# AIRZAI_BASE_BD_REVC_Sheet1.net
KiCad netlist of a schematic drawn in Altium Designer
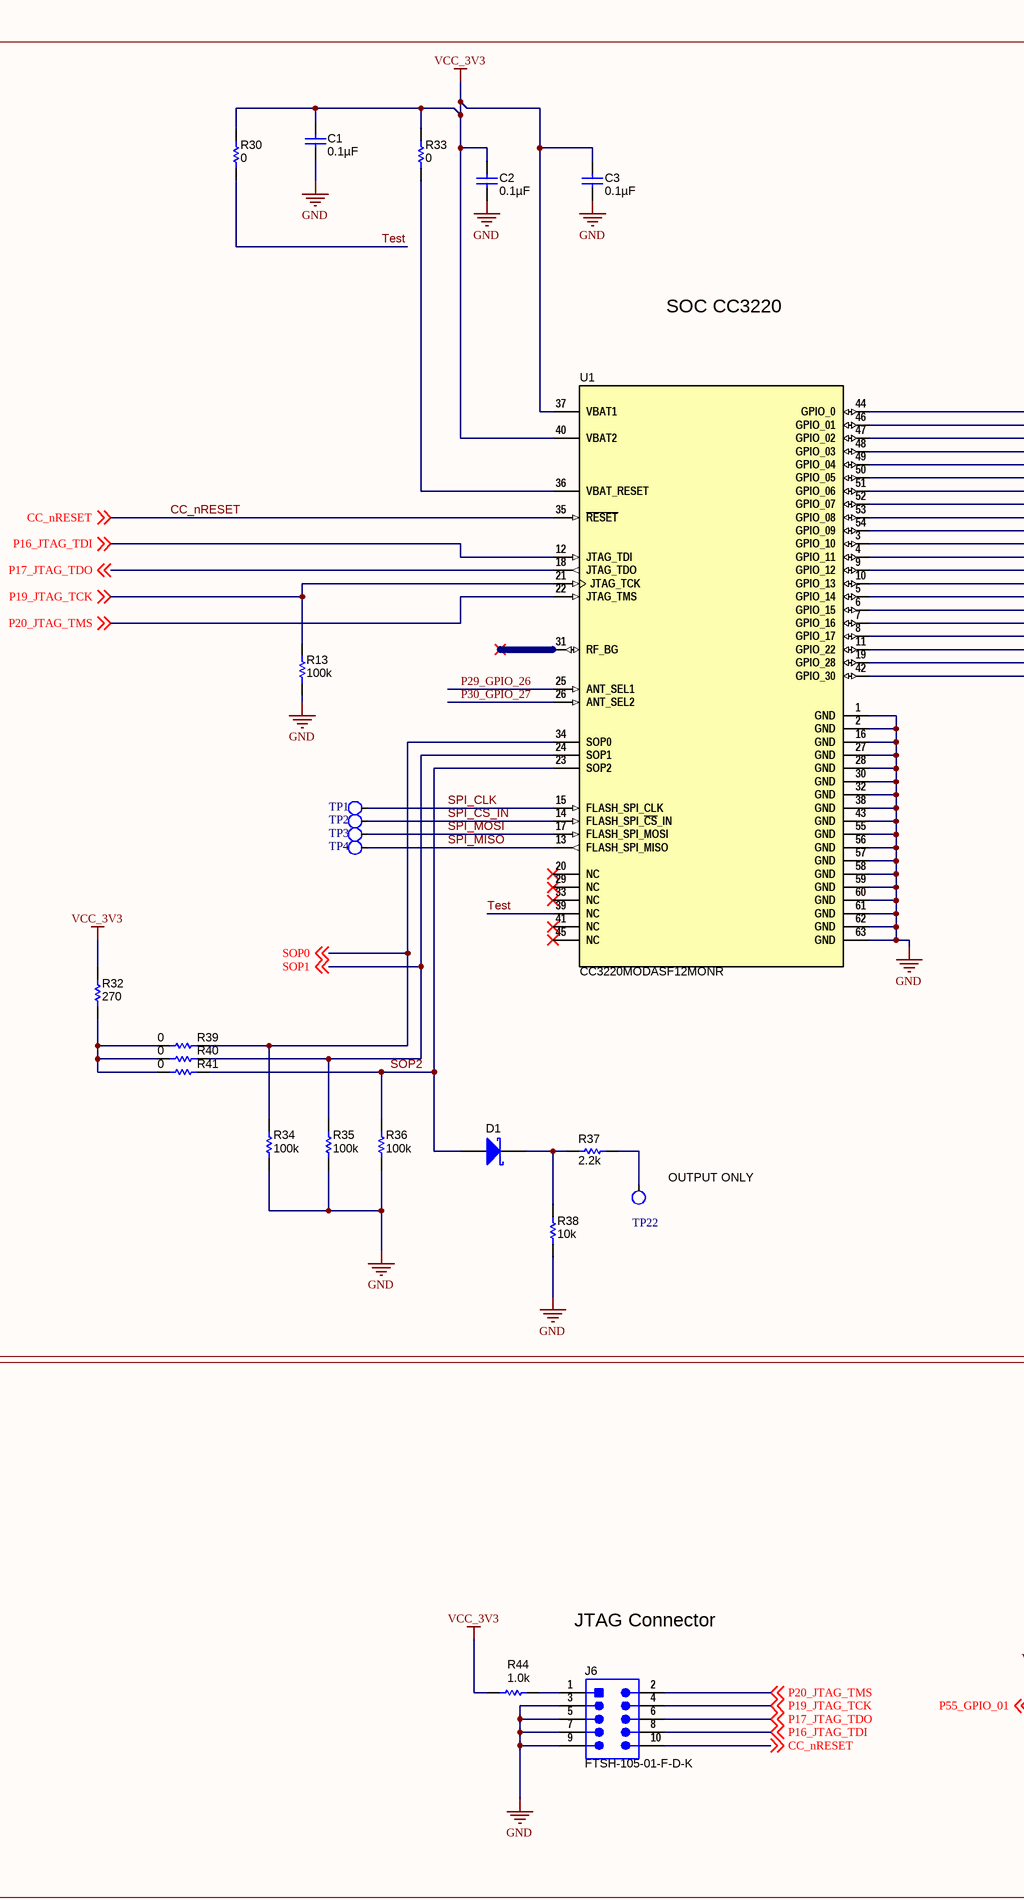
[diagram p0: AIRZAI_BASE_BD_REVC Sheet1.SchDoc, left]
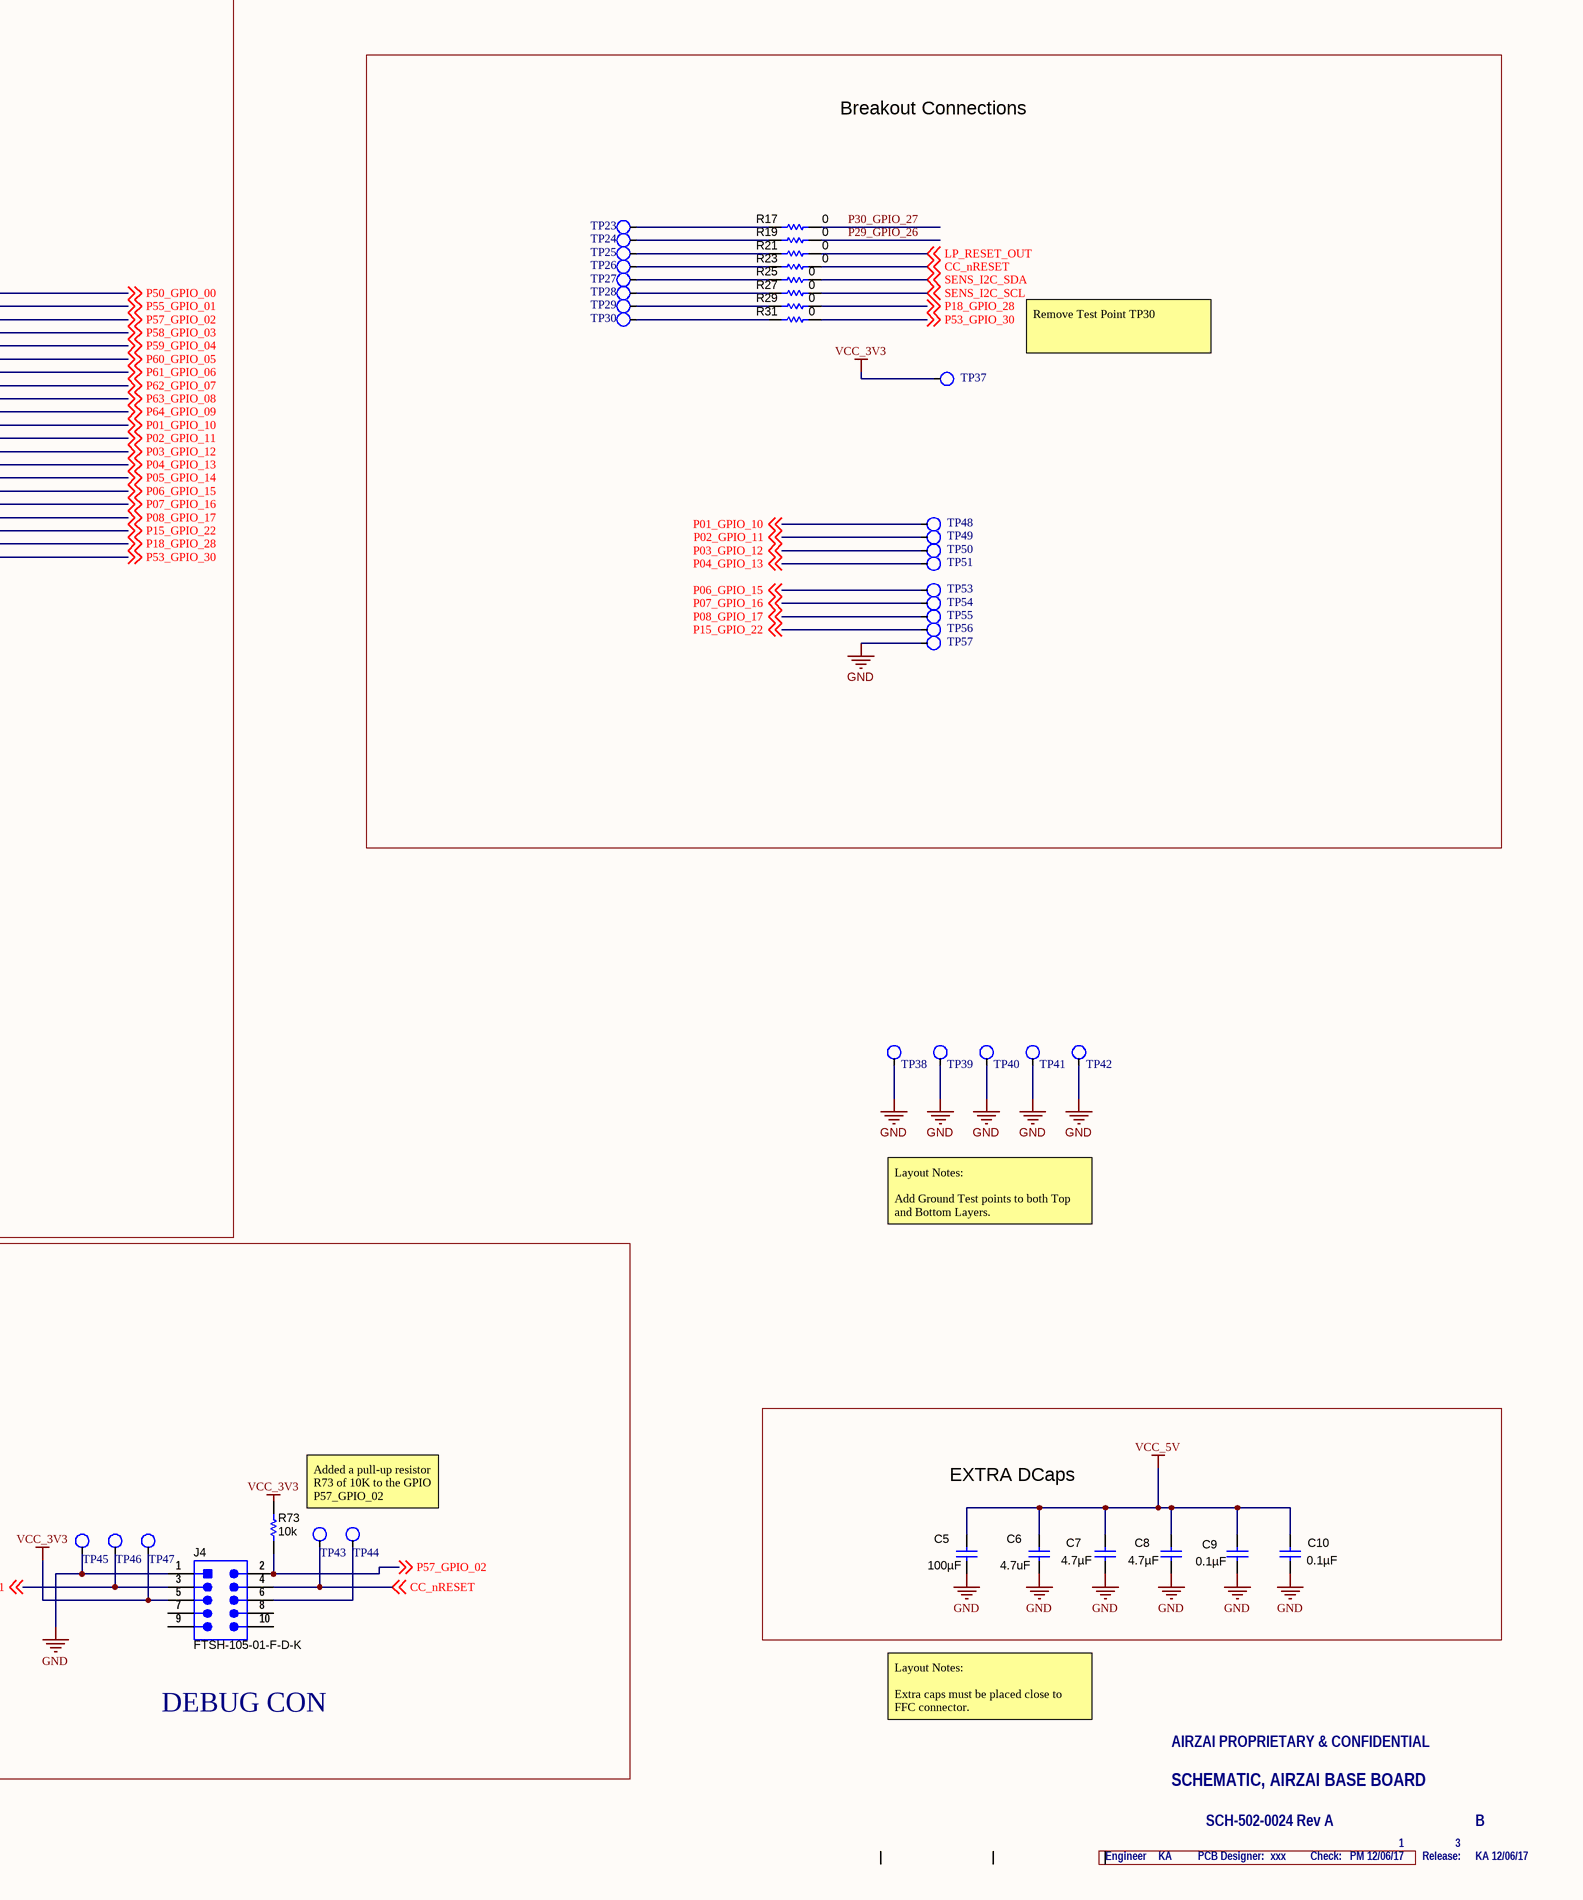
[diagram p1: AIRZAI_BASE_BD_REVC Sheet1.SchDoc, right]

(export (version "E")
  (design (tool "Eeschema 10.0.6"))
  (components
    (comp (ref "C1")
      (value "GRM155R61A104KA01D")
      (footprint "0402")
      (description "CAP, CERM, 0.1 µF, 10 V, +/- 10%, X5R, 0402")
      (fields
        (field (name "VALUEDISPLAYED") "0.1µF")
        (field (name "MANUFACTURER") "MuRata")
        (field (name "PUBLISHER") "Texas Instruments")
      )
      (libsource (lib "Capacitor_Ceramic") (part "GRM155R61A104KA01D"))
    )
    (comp (ref "C2")
      (value "GRM155R61A104KA01D")
      (footprint "0402")
      (description "CAP, CERM, 0.1 µF, 10 V, +/- 10%, X5R, 0402")
      (fields
        (field (name "VALUEDISPLAYED") "0.1µF")
        (field (name "MANUFACTURER") "MuRata")
        (field (name "PUBLISHER") "Texas Instruments")
      )
      (libsource (lib "Capacitor_Ceramic") (part "GRM155R61A104KA01D"))
    )
    (comp (ref "C3")
      (value "GRM155R61A104KA01D")
      (footprint "0402")
      (description "CAP, CERM, 0.1 µF, 10 V, +/- 10%, X5R, 0402")
      (fields
        (field (name "VALUEDISPLAYED") "0.1µF")
        (field (name "MANUFACTURER") "MuRata")
        (field (name "PUBLISHER") "Texas Instruments")
      )
      (libsource (lib "Capacitor_Ceramic") (part "GRM155R61A104KA01D"))
    )
    (comp (ref "C5")
      (value "GRM31CR60J107ME39L")
      (footprint "1206_180")
      (description "CAP, CERM, 100 µF, 6.3 V, +/- 20%, X5R, 1206")
      (fields
        (field (name "VALUEDISPLAYED") "100µF")
        (field (name "MANUFACTURER") "MuRata")
        (field (name "PUBLISHER") "Texas Instruments")
      )
      (libsource (lib "Capacitor_Ceramic") (part "GRM31CR60J107ME39L"))
    )
    (comp (ref "C6")
      (value "4.7uF")
      (footprint "SM0402_BTD.1SM_ACT_H55_CAP_WSS")
      (description "CAP, CERM, 4.7 µF, 6.3 V, +/- 20%, X5R, 0402")
      (fields (field (name "PARTNUMBER") "C1005X5R0J475M050BC") (field (name "MANUFACTURER") "TDK"))
      (libsource (lib "Capacitor_Ceramic") (part "C1005X5R0J475M050BC"))
    )
    (comp (ref "C7")
      (value "C1005X5R0J475M050BC")
      (footprint "SM0402_BTD.1SM_ACT_H55_CAP_WSS")
      (description "CAP, CERM, 4.7 µF, 6.3 V, +/- 20%, X5R, 0402")
      (fields
        (field (name "VALUEDISPLAYED") "4.7µF")
        (field (name "MANUFACTURER") "TDK")
        (field (name "PUBLISHER") "Texas Instruments")
      )
      (libsource (lib "Capacitor_Ceramic") (part "C1005X5R0J475M050BC"))
    )
    (comp (ref "C8")
      (value "C1005X5R0J475M050BC")
      (footprint "SM0402_BTD.1SM_ACT_H55_CAP_WSS")
      (description "CAP, CERM, 4.7 µF, 6.3 V, +/- 20%, X5R, 0402")
      (fields
        (field (name "VALUEDISPLAYED") "4.7µF")
        (field (name "MANUFACTURER") "TDK")
        (field (name "PUBLISHER") "Texas Instruments")
      )
      (libsource (lib "Capacitor_Ceramic") (part "C1005X5R0J475M050BC"))
    )
    (comp (ref "C9")
      (value "C1005X5R1A104K050BA")
      (footprint "SM0402_BTD.1SM_ACT_H55_CAP_WSS")
      (description "CAP, CERM, 0.1 µF, 10 V, +/- 10%, X5R, 0402")
      (fields
        (field (name "VALUEDISPLAYED") "0.1µF")
        (field (name "MANUFACTURER") "TDK")
        (field (name "PUBLISHER") "Texas Instruments")
      )
      (libsource (lib "Capacitor_Ceramic") (part "C1005X5R1A104K050BA"))
    )
    (comp (ref "C10")
      (value "C1005X5R1A104K050BA")
      (footprint "SM0402_BTD.1SM_ACT_H55_CAP_WSS")
      (description "CAP, CERM, 0.1 µF, 10 V, +/- 10%, X5R, 0402")
      (fields
        (field (name "VALUEDISPLAYED") "0.1µF")
        (field (name "MANUFACTURER") "TDK")
        (field (name "PUBLISHER") "Texas Instruments")
      )
      (libsource (lib "Capacitor_Ceramic") (part "C1005X5R1A104K050BA"))
    )
    (comp (ref "D1")
      (value "CD0603-B00340")
      (footprint "Diode_0603")
      (description "Diode, Schottky, 45 V, 0.03 A, 0603 Diode")
      (fields (field (name "MANUFACTURER") "Bourns") (field (name "PUBLISHER") "Texas Instruments"))
      (libsource (lib "Diode") (part "CD0603-B00340"))
    )
    (comp (ref "J4")
      (value "FTSH-105-01-F-D-K")
      (footprint "Samtec_FTSH-105-01-x-D-K")
      (description "Header, 1.27 mm, 5x2, Gold, TH")
      (fields
        (field (name "MANUFACTURER") "Samtec")
        (field (name "SYMBOLCREATOR") "a0412235")
        (field (name "PUBLISHER") "Texas Instruments")
      )
      (libsource (lib "Connectors_Samtec") (part "FTSH-105-01-F-D-K"))
    )
    (comp (ref "J6")
      (value "FTSH-105-01-F-D-K")
      (footprint "Samtec_FTSH-105-01-x-D-K")
      (description "Header, 1.27 mm, 5x2, Gold, TH")
      (fields
        (field (name "MANUFACTURER") "Samtec")
        (field (name "SYMBOLCREATOR") "a0412235")
        (field (name "PUBLISHER") "Texas Instruments")
      )
      (libsource (lib "Connectors_Samtec") (part "FTSH-105-01-F-D-K"))
    )
    (comp (ref "R13")
      (value "CRCW0402100KJNED")
      (footprint "0402")
      (description "RES, 100 k, 5%, 0.063 W, 0402")
      (fields
        (field (name "VALUEDISPLAYED") "100k")
        (field (name "MANUFACTURER") "Vishay-Dale")
        (field (name "PUBLISHER") "Texas Instruments")
      )
      (libsource (lib "Resistor_0402") (part "CRCW0402100KJNED"))
    )
    (comp (ref "R17")
      (value "ERJ-2GE0R00X")
      (footprint "0402")
      (description "RES, 0, 5%, 0.063 W, 0402")
      (fields
        (field (name "VALUEDISPLAYED") "0")
        (field (name "MANUFACTURER") "Panasonic")
        (field (name "PUBLISHER") "Texas Instruments")
      )
      (libsource (lib "Resistor_0402") (part "ERJ-2GE0R00X"))
    )
    (comp (ref "R19")
      (value "ERJ-2GE0R00X")
      (footprint "0402")
      (description "RES, 0, 5%, 0.063 W, 0402")
      (fields
        (field (name "VALUEDISPLAYED") "0")
        (field (name "MANUFACTURER") "Panasonic")
        (field (name "PUBLISHER") "Texas Instruments")
      )
      (libsource (lib "Resistor_0402") (part "ERJ-2GE0R00X"))
    )
    (comp (ref "R21")
      (value "ERJ-2GE0R00X")
      (footprint "0402")
      (description "RES, 0, 5%, 0.063 W, 0402")
      (fields
        (field (name "VALUEDISPLAYED") "0")
        (field (name "MANUFACTURER") "Panasonic")
        (field (name "PUBLISHER") "Texas Instruments")
      )
      (libsource (lib "Resistor_0402") (part "ERJ-2GE0R00X"))
    )
    (comp (ref "R23")
      (value "ERJ-2GE0R00X")
      (footprint "0402")
      (description "RES, 0, 5%, 0.063 W, 0402")
      (fields
        (field (name "VALUEDISPLAYED") "0")
        (field (name "MANUFACTURER") "Panasonic")
        (field (name "PUBLISHER") "Texas Instruments")
      )
      (libsource (lib "Resistor_0402") (part "ERJ-2GE0R00X"))
    )
    (comp (ref "R25")
      (value "ERJ-2GE0R00X")
      (footprint "0402")
      (description "RES, 0, 5%, 0.063 W, 0402")
      (fields
        (field (name "VALUEDISPLAYED") "0")
        (field (name "MANUFACTURER") "Panasonic")
        (field (name "PUBLISHER") "Texas Instruments")
      )
      (libsource (lib "Resistor_0402") (part "ERJ-2GE0R00X"))
    )
    (comp (ref "R27")
      (value "ERJ-2GE0R00X")
      (footprint "0402")
      (description "RES, 0, 5%, 0.063 W, 0402")
      (fields
        (field (name "VALUEDISPLAYED") "0")
        (field (name "MANUFACTURER") "Panasonic")
        (field (name "PUBLISHER") "Texas Instruments")
      )
      (libsource (lib "Resistor_0402") (part "ERJ-2GE0R00X"))
    )
    (comp (ref "R29")
      (value "ERJ-2GE0R00X")
      (footprint "0402")
      (description "RES, 0, 5%, 0.063 W, 0402")
      (fields
        (field (name "VALUEDISPLAYED") "0")
        (field (name "MANUFACTURER") "Panasonic")
        (field (name "PUBLISHER") "Texas Instruments")
      )
      (libsource (lib "Resistor_0402") (part "ERJ-2GE0R00X"))
    )
    (comp (ref "R30")
      (value "RC0603JR-070RL")
      (footprint "0603")
      (description "RES, 0, 5%, 0.1 W, 0603")
      (fields
        (field (name "VALUEDISPLAYED") "0")
        (field (name "MANUFACTURER") "Yageo")
        (field (name "TOLERANCE") "1%")
      )
      (libsource (lib "Resistor_0402") (part "ERJ-2GE0R00X"))
    )
    (comp (ref "R31")
      (value "ERJ-2GE0R00X")
      (footprint "0402")
      (description "RES, 0, 5%, 0.063 W, 0402")
      (fields
        (field (name "VALUEDISPLAYED") "0")
        (field (name "MANUFACTURER") "Panasonic")
        (field (name "PUBLISHER") "Texas Instruments")
      )
      (libsource (lib "Resistor_0402") (part "ERJ-2GE0R00X"))
    )
    (comp (ref "R32")
      (value "CRCW0402270RJNED")
      (footprint "0402")
      (description "RES, 270, 5%, 0.063 W, 0402")
      (fields
        (field (name "VALUEDISPLAYED") "270")
        (field (name "MANUFACTURER") "Vishay-Dale")
        (field (name "PUBLISHER") "Texas Instruments")
      )
      (libsource (lib "Resistor_0402") (part "CRCW0402270RJNED"))
    )
    (comp (ref "R33")
      (value "RC0603JR-070RL")
      (footprint "0603")
      (description "RES, 0, 5%, 0.1 W, 0603")
      (fields
        (field (name "VALUEDISPLAYED") "0")
        (field (name "MANUFACTURER") "Yageo")
        (field (name "TOLERANCE") "1%")
      )
      (libsource (lib "Resistor_0402") (part "ERJ-2GE0R00X"))
    )
    (comp (ref "R34")
      (value "CRCW0402100KJNED")
      (footprint "0402")
      (description "RES, 100 k, 5%, 0.063 W, 0402")
      (fields
        (field (name "VALUEDISPLAYED") "100k")
        (field (name "MANUFACTURER") "Vishay-Dale")
        (field (name "PUBLISHER") "Texas Instruments")
      )
      (libsource (lib "Resistor_0402") (part "CRCW0402100KJNED"))
    )
    (comp (ref "R35")
      (value "CRCW0402100KJNED")
      (footprint "0402")
      (description "RES, 100 k, 5%, 0.063 W, 0402")
      (fields
        (field (name "VALUEDISPLAYED") "100k")
        (field (name "MANUFACTURER") "Vishay-Dale")
        (field (name "PUBLISHER") "Texas Instruments")
      )
      (libsource (lib "Resistor_0402") (part "CRCW0402100KJNED"))
    )
    (comp (ref "R36")
      (value "CRCW0402100KJNED")
      (footprint "0402")
      (description "RES, 100 k, 5%, 0.063 W, 0402")
      (fields
        (field (name "VALUEDISPLAYED") "100k")
        (field (name "MANUFACTURER") "Vishay-Dale")
        (field (name "PUBLISHER") "Texas Instruments")
      )
      (libsource (lib "Resistor_0402") (part "CRCW0402100KJNED"))
    )
    (comp (ref "R37")
      (value "CRCW04022K20JNED")
      (footprint "0402")
      (description "RES, 2.2 k, 5%, 0.063 W, 0402")
      (fields
        (field (name "VALUEDISPLAYED") "2.2k")
        (field (name "MANUFACTURER") "Vishay-Dale")
        (field (name "PUBLISHER") "Texas Instruments")
      )
      (libsource (lib "Resistor_0402") (part "CRCW04022K20JNED"))
    )
    (comp (ref "R38")
      (value "CRCW040210K0JNED")
      (footprint "0402")
      (description "RES, 10 k, 5%, 0.063 W, 0402")
      (fields
        (field (name "VALUEDISPLAYED") "10k")
        (field (name "MANUFACTURER") "Vishay-Dale")
        (field (name "PUBLISHER") "Texas Instruments")
      )
      (libsource (lib "Resistor_0402") (part "CRCW040210K0JNED"))
    )
    (comp (ref "R39")
      (value "RC0603JR-070RL")
      (footprint "0603")
      (description "RES, 0, 5%, 0.1 W, 0603")
      (fields
        (field (name "VALUEDISPLAYED") "0")
        (field (name "MANUFACTURER") "Yageo")
        (field (name "TOLERANCE") "1%")
      )
      (libsource (lib "Resistor_0402") (part "ERJ-2GE0R00X"))
    )
    (comp (ref "R40")
      (value "RC0603JR-070RL")
      (footprint "0603")
      (description "RES, 0, 5%, 0.1 W, 0603")
      (fields
        (field (name "VALUEDISPLAYED") "0")
        (field (name "MANUFACTURER") "Yageo")
        (field (name "TOLERANCE") "1%")
      )
      (libsource (lib "Resistor_0402") (part "ERJ-2GE0R00X"))
    )
    (comp (ref "R41")
      (value "RC0603JR-070RL")
      (footprint "0603")
      (description "RES, 0, 5%, 0.1 W, 0603")
      (fields
        (field (name "VALUEDISPLAYED") "0")
        (field (name "MANUFACTURER") "Yageo")
        (field (name "TOLERANCE") "1%")
      )
      (libsource (lib "Resistor_0402") (part "ERJ-2GE0R00X"))
    )
    (comp (ref "R44")
      (value "CRCW04021K00JNED")
      (footprint "0402")
      (description "RES, 1.0 k, 5%, 0.063 W, 0402")
      (fields
        (field (name "VALUEDISPLAYED") "1.0k")
        (field (name "MANUFACTURER") "Vishay-Dale")
        (field (name "PUBLISHER") "Texas Instruments")
      )
      (libsource (lib "Resistor_0402") (part "CRCW04021K00JNED"))
    )
    (comp (ref "R73")
      (value "CRCW040210K0JNED")
      (footprint "0402")
      (description "RES, 10 k, 5%, 0.063 W, 0402")
      (fields
        (field (name "VALUEDISPLAYED") "10k")
        (field (name "MANUFACTURER") "Vishay-Dale")
        (field (name "PUBLISHER") "Texas Instruments")
      )
      (libsource (lib "Resistor_0402") (part "CRCW040210K0JNED"))
    )
    (comp (ref "TP1")
      (value "WIREPT")
      (footprint "TP_0.9MM")
      (libsource (lib "EAGLE_CAD_Library") (part "WIREPT"))
    )
    (comp (ref "TP2")
      (value "WIREPT")
      (footprint "TP_0.9MM")
      (libsource (lib "EAGLE_CAD_Library") (part "WIREPT"))
    )
    (comp (ref "TP3")
      (value "WIREPT")
      (footprint "TP_0.9MM")
      (libsource (lib "EAGLE_CAD_Library") (part "WIREPT"))
    )
    (comp (ref "TP4")
      (value "WIREPT")
      (footprint "TP_0.9MM")
      (libsource (lib "EAGLE_CAD_Library") (part "WIREPT"))
    )
    (comp (ref "TP22")
      (value "WIREPT")
      (footprint "TP_0.9MM")
      (libsource (lib "EAGLE_CAD_Library") (part "WIREPT"))
    )
    (comp (ref "TP23")
      (value "WIREPT")
      (footprint "TP_0.9MM")
      (libsource (lib "EAGLE_CAD_Library") (part "WIREPT"))
    )
    (comp (ref "TP24")
      (value "WIREPT")
      (footprint "TP_0.9MM")
      (libsource (lib "EAGLE_CAD_Library") (part "WIREPT"))
    )
    (comp (ref "TP25")
      (value "WIREPT")
      (footprint "TP_0.9MM")
      (libsource (lib "EAGLE_CAD_Library") (part "WIREPT"))
    )
    (comp (ref "TP26")
      (value "WIREPT")
      (footprint "TP_0.9MM")
      (libsource (lib "EAGLE_CAD_Library") (part "WIREPT"))
    )
    (comp (ref "TP27")
      (value "WIREPT")
      (footprint "TP_0.9MM")
      (libsource (lib "EAGLE_CAD_Library") (part "WIREPT"))
    )
    (comp (ref "TP28")
      (value "WIREPT")
      (footprint "TP_0.9MM")
      (libsource (lib "EAGLE_CAD_Library") (part "WIREPT"))
    )
    (comp (ref "TP29")
      (value "WIREPT")
      (footprint "TP_0.9MM")
      (libsource (lib "EAGLE_CAD_Library") (part "WIREPT"))
    )
    (comp (ref "TP30")
      (value "WIREPT")
      (footprint "TP_0.9MM")
      (libsource (lib "EAGLE_CAD_Library") (part "WIREPT"))
    )
    (comp (ref "TP37")
      (value "WIREPT")
      (footprint "TP_0.9MM")
      (libsource (lib "EAGLE_CAD_Library") (part "WIREPT"))
    )
    (comp (ref "TP38")
      (value "WIREPT")
      (footprint "TP_0.9MM")
      (libsource (lib "EAGLE_CAD_Library") (part "WIREPT"))
    )
    (comp (ref "TP39")
      (value "WIREPT")
      (footprint "TP_0.9MM")
      (libsource (lib "EAGLE_CAD_Library") (part "WIREPT"))
    )
    (comp (ref "TP40")
      (value "WIREPT")
      (footprint "TP_0.9MM")
      (libsource (lib "EAGLE_CAD_Library") (part "WIREPT"))
    )
    (comp (ref "TP41")
      (value "WIREPT")
      (footprint "TP_0.9MM")
      (libsource (lib "EAGLE_CAD_Library") (part "WIREPT"))
    )
    (comp (ref "TP42")
      (value "WIREPT")
      (footprint "TP_0.9MM")
      (libsource (lib "EAGLE_CAD_Library") (part "WIREPT"))
    )
    (comp (ref "TP43")
      (value "WIREPT")
      (footprint "TP_0.9MM")
      (libsource (lib "EAGLE_CAD_Library") (part "WIREPT"))
    )
    (comp (ref "TP44")
      (value "WIREPT")
      (footprint "TP_0.9MM")
      (libsource (lib "EAGLE_CAD_Library") (part "WIREPT"))
    )
    (comp (ref "TP45")
      (value "WIREPT")
      (footprint "TP_0.9MM")
      (libsource (lib "EAGLE_CAD_Library") (part "WIREPT"))
    )
    (comp (ref "TP46")
      (value "WIREPT")
      (footprint "TP_0.9MM")
      (libsource (lib "EAGLE_CAD_Library") (part "WIREPT"))
    )
    (comp (ref "TP47")
      (value "WIREPT")
      (footprint "TP_0.9MM")
      (libsource (lib "EAGLE_CAD_Library") (part "WIREPT"))
    )
    (comp (ref "TP48")
      (value "WIREPT")
      (footprint "TP_0.9MM")
      (libsource (lib "EAGLE_CAD_Library") (part "WIREPT"))
    )
    (comp (ref "TP49")
      (value "WIREPT")
      (footprint "TP_0.9MM")
      (libsource (lib "EAGLE_CAD_Library") (part "WIREPT"))
    )
    (comp (ref "TP50")
      (value "WIREPT")
      (footprint "TP_0.9MM")
      (libsource (lib "EAGLE_CAD_Library") (part "WIREPT"))
    )
    (comp (ref "TP51")
      (value "WIREPT")
      (footprint "TP_0.9MM")
      (libsource (lib "EAGLE_CAD_Library") (part "WIREPT"))
    )
    (comp (ref "TP53")
      (value "WIREPT")
      (footprint "TP_0.9MM")
      (libsource (lib "EAGLE_CAD_Library") (part "WIREPT"))
    )
    (comp (ref "TP54")
      (value "WIREPT")
      (footprint "TP_0.9MM")
      (libsource (lib "EAGLE_CAD_Library") (part "WIREPT"))
    )
    (comp (ref "TP55")
      (value "WIREPT")
      (footprint "TP_0.9MM")
      (libsource (lib "EAGLE_CAD_Library") (part "WIREPT"))
    )
    (comp (ref "TP56")
      (value "WIREPT")
      (footprint "TP_0.9MM")
      (libsource (lib "EAGLE_CAD_Library") (part "WIREPT"))
    )
    (comp (ref "TP57")
      (value "WIREPT")
      (footprint "TP_0.9MM")
      (libsource (lib "EAGLE_CAD_Library") (part "WIREPT"))
    )
    (comp (ref "U1")
      (value "CC3220MODASF12MONR")
      (footprint "MON0063A")
      (fields
        (field (name "ALTERNATE PARTNUMBER") "XCC3220MODASF12MONR")
        (field (name "MANUFACTURER") "Texas Instruments")
        (field (name "SYMBOLCREATOR") "Altium")
        (field (name "PUBLISHER") "Texas Instruments")
      )
      (libsource (lib "TI_Pre_RTM") (part "CC3220MODASF12MONR"))
    )
  )
  (nets
    (net (code "1") (name "/P29_GPIO_26") (class "Default")
      (node (ref "R19") (pin "2") (pinfunction "2_2") (pintype "passive"))
      (node (ref "U1") (pin "25") (pinfunction "ANT_SEL1_25") (pintype "input"))
    )
    (net (code "2") (name "/P30_GPIO_27") (class "Default")
      (node (ref "R17") (pin "2") (pinfunction "2_2") (pintype "passive"))
      (node (ref "U1") (pin "26") (pinfunction "ANT_SEL2_26") (pintype "input"))
    )
    (net (code "3") (name "/SOP2") (class "Default")
      (node (ref "D1") (pin "2") (pinfunction "A_2") (pintype "passive"))
      (node (ref "R36") (pin "1") (pinfunction "1_1") (pintype "passive"))
      (node (ref "R41") (pin "1") (pinfunction "1_1") (pintype "passive"))
      (node (ref "U1") (pin "23") (pinfunction "SOP2_23") (pintype "passive"))
    )
    (net (code "4") (name "/SPI_CLK") (class "Default")
      (node (ref "TP1") (pin "1") (pinfunction "1_1") (pintype "passive"))
      (node (ref "U1") (pin "15") (pinfunction "FLASH_SPI_CLK_15") (pintype "input"))
    )
    (net (code "5") (name "/SPI_CS_IN") (class "Default")
      (node (ref "TP2") (pin "1") (pinfunction "1_1") (pintype "passive"))
      (node (ref "U1") (pin "14") (pinfunction "FLASH_SPI_~{CS}_IN_14") (pintype "input"))
    )
    (net (code "6") (name "/SPI_MISO") (class "Default")
      (node (ref "TP4") (pin "1") (pinfunction "1_1") (pintype "passive"))
      (node (ref "U1") (pin "13") (pinfunction "FLASH_SPI_MISO_13") (pintype "output"))
    )
    (net (code "7") (name "/SPI_MOSI") (class "Default")
      (node (ref "TP3") (pin "1") (pinfunction "1_1") (pintype "passive"))
      (node (ref "U1") (pin "17") (pinfunction "FLASH_SPI_MOSI_17") (pintype "input"))
    )
    (net (code "8") (name "/Test") (class "Default")
      (node (ref "R30") (pin "1") (pinfunction "1_1") (pintype "passive"))
      (node (ref "U1") (pin "39") (pinfunction "NC_39") (pintype "passive"))
    )
    (net (code "9") (name "CC_nRESET") (class "Default")
      (node (ref "J4") (pin "4") (pinfunction "4_4") (pintype "passive"))
      (node (ref "J6") (pin "10") (pinfunction "10_10") (pintype "passive"))
      (node (ref "R23") (pin "2") (pinfunction "2_2") (pintype "passive"))
      (node (ref "TP43") (pin "1") (pinfunction "1_1") (pintype "passive"))
      (node (ref "U1") (pin "35") (pinfunction "RESET_35") (pintype "input"))
    )
    (net (code "10") (name "GND") (class "Default")
      (node (ref "C1") (pin "2") (pinfunction "2_2") (pintype "passive"))
      (node (ref "C10") (pin "2") (pinfunction "2_2") (pintype "passive"))
      (node (ref "C2") (pin "2") (pinfunction "2_2") (pintype "passive"))
      (node (ref "C3") (pin "2") (pinfunction "2_2") (pintype "passive"))
      (node (ref "C5") (pin "2") (pinfunction "2_2") (pintype "passive"))
      (node (ref "C6") (pin "2") (pinfunction "2_2") (pintype "passive"))
      (node (ref "C7") (pin "2") (pinfunction "2_2") (pintype "passive"))
      (node (ref "C8") (pin "2") (pinfunction "2_2") (pintype "passive"))
      (node (ref "C9") (pin "2") (pinfunction "2_2") (pintype "passive"))
      (node (ref "J4") (pin "1") (pinfunction "1_1") (pintype "passive"))
      (node (ref "J6") (pin "3") (pinfunction "3_3") (pintype "passive"))
      (node (ref "J6") (pin "5") (pinfunction "5_5") (pintype "passive"))
      (node (ref "J6") (pin "7") (pinfunction "7_7") (pintype "passive"))
      (node (ref "J6") (pin "9") (pinfunction "9_9") (pintype "passive"))
      (node (ref "R13") (pin "2") (pinfunction "2_2") (pintype "passive"))
      (node (ref "R34") (pin "1") (pinfunction "1_1") (pintype "passive"))
      (node (ref "R35") (pin "2") (pinfunction "2_2") (pintype "passive"))
      (node (ref "R36") (pin "2") (pinfunction "2_2") (pintype "passive"))
      (node (ref "R38") (pin "2") (pinfunction "2_2") (pintype "passive"))
      (node (ref "TP38") (pin "1") (pinfunction "1_1") (pintype "passive"))
      (node (ref "TP39") (pin "1") (pinfunction "1_1") (pintype "passive"))
      (node (ref "TP40") (pin "1") (pinfunction "1_1") (pintype "passive"))
      (node (ref "TP41") (pin "1") (pinfunction "1_1") (pintype "passive"))
      (node (ref "TP42") (pin "1") (pinfunction "1_1") (pintype "passive"))
      (node (ref "TP45") (pin "1") (pinfunction "1_1") (pintype "passive"))
      (node (ref "TP57") (pin "1") (pinfunction "1_1") (pintype "passive"))
      (node (ref "U1") (pin "1") (pinfunction "GND_1") (pintype "power_in"))
      (node (ref "U1") (pin "16") (pinfunction "GND_16") (pintype "power_in"))
      (node (ref "U1") (pin "2") (pinfunction "GND_2") (pintype "power_in"))
      (node (ref "U1") (pin "27") (pinfunction "GND_27") (pintype "power_in"))
      (node (ref "U1") (pin "28") (pinfunction "GND_28") (pintype "power_in"))
      (node (ref "U1") (pin "30") (pinfunction "GND_30") (pintype "power_in"))
      (node (ref "U1") (pin "32") (pinfunction "GND_32") (pintype "power_in"))
      (node (ref "U1") (pin "38") (pinfunction "GND_38") (pintype "power_in"))
      (node (ref "U1") (pin "43") (pinfunction "GND_43") (pintype "power_in"))
      (node (ref "U1") (pin "55") (pinfunction "GND_55") (pintype "power_in"))
      (node (ref "U1") (pin "56") (pinfunction "GND_56") (pintype "power_in"))
      (node (ref "U1") (pin "57") (pinfunction "GND_57") (pintype "power_in"))
      (node (ref "U1") (pin "58") (pinfunction "GND_58") (pintype "power_in"))
      (node (ref "U1") (pin "59") (pinfunction "GND_59") (pintype "power_in"))
      (node (ref "U1") (pin "60") (pinfunction "GND_60") (pintype "power_in"))
      (node (ref "U1") (pin "61") (pinfunction "GND_61") (pintype "power_in"))
      (node (ref "U1") (pin "62") (pinfunction "GND_62") (pintype "power_in"))
      (node (ref "U1") (pin "63") (pinfunction "GND_63") (pintype "power_in"))
    )
    (net (code "11") (name "LP_RESET_OUT") (class "Default")
      (node (ref "R21") (pin "2") (pinfunction "2_2") (pintype "passive"))
    )
    (net (code "12") (name "Net-(D1-K)") (class "Default")
      (node (ref "D1") (pin "1") (pinfunction "K_1") (pintype "passive"))
      (node (ref "R37") (pin "1") (pinfunction "1_1") (pintype "passive"))
      (node (ref "R38") (pin "1") (pinfunction "1_1") (pintype "passive"))
    )
    (net (code "13") (name "Net-(J4-Pad6)") (class "Default")
      (node (ref "J4") (pin "6") (pinfunction "6_6") (pintype "passive"))
      (node (ref "TP44") (pin "1") (pinfunction "1_1") (pintype "passive"))
    )
    (net (code "14") (name "Net-(J6-Pad1)") (class "Default")
      (node (ref "J6") (pin "1") (pinfunction "1_1") (pintype "passive"))
      (node (ref "R44") (pin "2") (pinfunction "2_2") (pintype "passive"))
    )
    (net (code "15") (name "Net-(R17-Pad1)") (class "Default")
      (node (ref "R17") (pin "1") (pinfunction "1_1") (pintype "passive"))
      (node (ref "TP23") (pin "1") (pinfunction "1_1") (pintype "passive"))
    )
    (net (code "16") (name "Net-(R19-Pad1)") (class "Default")
      (node (ref "R19") (pin "1") (pinfunction "1_1") (pintype "passive"))
      (node (ref "TP24") (pin "1") (pinfunction "1_1") (pintype "passive"))
    )
    (net (code "17") (name "Net-(R21-Pad1)") (class "Default")
      (node (ref "R21") (pin "1") (pinfunction "1_1") (pintype "passive"))
      (node (ref "TP25") (pin "1") (pinfunction "1_1") (pintype "passive"))
    )
    (net (code "18") (name "Net-(R23-Pad1)") (class "Default")
      (node (ref "R23") (pin "1") (pinfunction "1_1") (pintype "passive"))
      (node (ref "TP26") (pin "1") (pinfunction "1_1") (pintype "passive"))
    )
    (net (code "19") (name "Net-(R25-Pad1)") (class "Default")
      (node (ref "R25") (pin "1") (pinfunction "1_1") (pintype "passive"))
      (node (ref "TP27") (pin "1") (pinfunction "1_1") (pintype "passive"))
    )
    (net (code "20") (name "Net-(R27-Pad1)") (class "Default")
      (node (ref "R27") (pin "1") (pinfunction "1_1") (pintype "passive"))
      (node (ref "TP28") (pin "1") (pinfunction "1_1") (pintype "passive"))
    )
    (net (code "21") (name "Net-(R29-Pad1)") (class "Default")
      (node (ref "R29") (pin "1") (pinfunction "1_1") (pintype "passive"))
      (node (ref "TP29") (pin "1") (pinfunction "1_1") (pintype "passive"))
    )
    (net (code "22") (name "Net-(R31-Pad1)") (class "Default")
      (node (ref "R31") (pin "1") (pinfunction "1_1") (pintype "passive"))
      (node (ref "TP30") (pin "1") (pinfunction "1_1") (pintype "passive"))
    )
    (net (code "23") (name "Net-(R32-Pad2)") (class "Default")
      (node (ref "R32") (pin "2") (pinfunction "2_2") (pintype "passive"))
      (node (ref "R39") (pin "2") (pinfunction "2_2") (pintype "passive"))
      (node (ref "R40") (pin "2") (pinfunction "2_2") (pintype "passive"))
      (node (ref "R41") (pin "2") (pinfunction "2_2") (pintype "passive"))
    )
    (net (code "24") (name "Net-(R37-Pad2)") (class "Default")
      (node (ref "R37") (pin "2") (pinfunction "2_2") (pintype "passive"))
      (node (ref "TP22") (pin "1") (pinfunction "1_1") (pintype "passive"))
    )
    (net (code "25") (name "Net-(U1-VBAT_RESET)") (class "Default")
      (node (ref "R33") (pin "1") (pinfunction "1_1") (pintype "passive"))
      (node (ref "U1") (pin "36") (pinfunction "VBAT_RESET_36") (pintype "passive"))
    )
    (net (code "26") (name "P01_GPIO_10") (class "Default")
      (node (ref "TP48") (pin "1") (pinfunction "1_1") (pintype "passive"))
      (node (ref "U1") (pin "3") (pinfunction "GPIO_10_3") (pintype "bidirectional"))
    )
    (net (code "27") (name "P02_GPIO_11") (class "Default")
      (node (ref "TP49") (pin "1") (pinfunction "1_1") (pintype "passive"))
      (node (ref "U1") (pin "4") (pinfunction "GPIO_11_4") (pintype "bidirectional"))
    )
    (net (code "28") (name "P03_GPIO_12") (class "Default")
      (node (ref "TP50") (pin "1") (pinfunction "1_1") (pintype "passive"))
      (node (ref "U1") (pin "9") (pinfunction "GPIO_12_9") (pintype "bidirectional"))
    )
    (net (code "29") (name "P04_GPIO_13") (class "Default")
      (node (ref "TP51") (pin "1") (pinfunction "1_1") (pintype "passive"))
      (node (ref "U1") (pin "10") (pinfunction "GPIO_13_10") (pintype "bidirectional"))
    )
    (net (code "30") (name "P05_GPIO_14") (class "Default")
      (node (ref "U1") (pin "5") (pinfunction "GPIO_14_5") (pintype "bidirectional"))
    )
    (net (code "31") (name "P06_GPIO_15") (class "Default")
      (node (ref "TP53") (pin "1") (pinfunction "1_1") (pintype "passive"))
      (node (ref "U1") (pin "6") (pinfunction "GPIO_15_6") (pintype "bidirectional"))
    )
    (net (code "32") (name "P07_GPIO_16") (class "Default")
      (node (ref "TP54") (pin "1") (pinfunction "1_1") (pintype "passive"))
      (node (ref "U1") (pin "7") (pinfunction "GPIO_16_7") (pintype "bidirectional"))
    )
    (net (code "33") (name "P08_GPIO_17") (class "Default")
      (node (ref "TP55") (pin "1") (pinfunction "1_1") (pintype "passive"))
      (node (ref "U1") (pin "8") (pinfunction "GPIO_17_8") (pintype "bidirectional"))
    )
    (net (code "34") (name "P15_GPIO_22") (class "Default")
      (node (ref "TP56") (pin "1") (pinfunction "1_1") (pintype "passive"))
      (node (ref "U1") (pin "11") (pinfunction "GPIO_22_11") (pintype "bidirectional"))
    )
    (net (code "35") (name "P16_JTAG_TDI") (class "Default")
      (node (ref "J6") (pin "8") (pinfunction "8_8") (pintype "passive"))
      (node (ref "U1") (pin "12") (pinfunction "JTAG_TDI_12") (pintype "input"))
    )
    (net (code "36") (name "P17_JTAG_TDO") (class "Default")
      (node (ref "J6") (pin "6") (pinfunction "6_6") (pintype "passive"))
      (node (ref "U1") (pin "18") (pinfunction "JTAG_TDO_18") (pintype "output"))
    )
    (net (code "37") (name "P18_GPIO_28") (class "Default")
      (node (ref "R29") (pin "2") (pinfunction "2_2") (pintype "passive"))
      (node (ref "U1") (pin "19") (pinfunction "GPIO_28_19") (pintype "bidirectional"))
    )
    (net (code "38") (name "P19_JTAG_TCK") (class "Default")
      (node (ref "J6") (pin "4") (pinfunction "4_4") (pintype "passive"))
      (node (ref "R13") (pin "1") (pinfunction "1_1") (pintype "passive"))
      (node (ref "U1") (pin "21") (pinfunction "JTAG_TCK_21") (pintype "input"))
    )
    (net (code "39") (name "P20_JTAG_TMS") (class "Default")
      (node (ref "J6") (pin "2") (pinfunction "2_2") (pintype "passive"))
      (node (ref "U1") (pin "22") (pinfunction "JTAG_TMS_22") (pintype "input"))
    )
    (net (code "40") (name "P50_GPIO_00") (class "Default")
      (node (ref "U1") (pin "44") (pinfunction "GPIO_0_44") (pintype "bidirectional"))
    )
    (net (code "41") (name "P53_GPIO_30") (class "Default")
      (node (ref "R31") (pin "2") (pinfunction "2_2") (pintype "passive"))
      (node (ref "U1") (pin "42") (pinfunction "GPIO_30_42") (pintype "bidirectional"))
    )
    (net (code "42") (name "P55_GPIO_01") (class "Default")
      (node (ref "J4") (pin "3") (pinfunction "3_3") (pintype "passive"))
      (node (ref "TP46") (pin "1") (pinfunction "1_1") (pintype "passive"))
      (node (ref "U1") (pin "46") (pinfunction "GPIO_01_46") (pintype "bidirectional"))
    )
    (net (code "43") (name "P57_GPIO_02") (class "Default")
      (node (ref "J4") (pin "2") (pinfunction "2_2") (pintype "passive"))
      (node (ref "R73") (pin "2") (pinfunction "2_2") (pintype "passive"))
      (node (ref "U1") (pin "47") (pinfunction "GPIO_02_47") (pintype "bidirectional"))
    )
    (net (code "44") (name "P58_GPIO_03") (class "Default")
      (node (ref "U1") (pin "48") (pinfunction "GPIO_03_48") (pintype "bidirectional"))
    )
    (net (code "45") (name "P59_GPIO_04") (class "Default")
      (node (ref "U1") (pin "49") (pinfunction "GPIO_04_49") (pintype "bidirectional"))
    )
    (net (code "46") (name "P60_GPIO_05") (class "Default")
      (node (ref "U1") (pin "50") (pinfunction "GPIO_05_50") (pintype "bidirectional"))
    )
    (net (code "47") (name "P61_GPIO_06") (class "Default")
      (node (ref "U1") (pin "51") (pinfunction "GPIO_06_51") (pintype "bidirectional"))
    )
    (net (code "48") (name "P62_GPIO_07") (class "Default")
      (node (ref "U1") (pin "52") (pinfunction "GPIO_07_52") (pintype "bidirectional"))
    )
    (net (code "49") (name "P63_GPIO_08") (class "Default")
      (node (ref "U1") (pin "53") (pinfunction "GPIO_08_53") (pintype "bidirectional"))
    )
    (net (code "50") (name "P64_GPIO_09") (class "Default")
      (node (ref "U1") (pin "54") (pinfunction "GPIO_09_54") (pintype "bidirectional"))
    )
    (net (code "51") (name "SENS_I2C_SCL") (class "Default")
      (node (ref "R27") (pin "2") (pinfunction "2_2") (pintype "passive"))
    )
    (net (code "52") (name "SENS_I2C_SDA") (class "Default")
      (node (ref "R25") (pin "2") (pinfunction "2_2") (pintype "passive"))
    )
    (net (code "53") (name "SOP0") (class "Default")
      (node (ref "R34") (pin "2") (pinfunction "2_2") (pintype "passive"))
      (node (ref "R39") (pin "1") (pinfunction "1_1") (pintype "passive"))
      (node (ref "U1") (pin "34") (pinfunction "SOP0_34") (pintype "passive"))
    )
    (net (code "54") (name "SOP1") (class "Default")
      (node (ref "R35") (pin "1") (pinfunction "1_1") (pintype "passive"))
      (node (ref "R40") (pin "1") (pinfunction "1_1") (pintype "passive"))
      (node (ref "U1") (pin "24") (pinfunction "SOP1_24") (pintype "passive"))
    )
    (net (code "55") (name "VCC_3V3") (class "Default")
      (node (ref "C1") (pin "1") (pinfunction "1_1") (pintype "passive"))
      (node (ref "C2") (pin "1") (pinfunction "1_1") (pintype "passive"))
      (node (ref "C3") (pin "1") (pinfunction "1_1") (pintype "passive"))
      (node (ref "J4") (pin "5") (pinfunction "5_5") (pintype "passive"))
      (node (ref "R30") (pin "2") (pinfunction "2_2") (pintype "passive"))
      (node (ref "R32") (pin "1") (pinfunction "1_1") (pintype "passive"))
      (node (ref "R33") (pin "2") (pinfunction "2_2") (pintype "passive"))
      (node (ref "R44") (pin "1") (pinfunction "1_1") (pintype "passive"))
      (node (ref "TP37") (pin "1") (pinfunction "1_1") (pintype "passive"))
      (node (ref "TP47") (pin "1") (pinfunction "1_1") (pintype "passive"))
      (node (ref "U1") (pin "37") (pinfunction "VBAT1_37") (pintype "power_in"))
      (node (ref "U1") (pin "40") (pinfunction "VBAT2_40") (pintype "power_in"))
    )
    (net (code "56") (name "VCC_5V") (class "Default")
      (node (ref "C10") (pin "1") (pinfunction "1_1") (pintype "passive"))
      (node (ref "C5") (pin "1") (pinfunction "1_1") (pintype "passive"))
      (node (ref "C6") (pin "1") (pinfunction "1_1") (pintype "passive"))
      (node (ref "C7") (pin "1") (pinfunction "1_1") (pintype "passive"))
      (node (ref "C8") (pin "1") (pinfunction "1_1") (pintype "passive"))
      (node (ref "C9") (pin "1") (pinfunction "1_1") (pintype "passive"))
    )
    (net (code "57") (name "unconnected-(J4-Pad7)") (class "Default")
      (node (ref "J4") (pin "7") (pinfunction "7_7") (pintype "passive"))
    )
    (net (code "58") (name "unconnected-(J4-Pad8)") (class "Default")
      (node (ref "J4") (pin "8") (pinfunction "8_8") (pintype "passive"))
    )
    (net (code "59") (name "unconnected-(J4-Pad9)") (class "Default")
      (node (ref "J4") (pin "9") (pinfunction "9_9") (pintype "passive"))
    )
    (net (code "60") (name "unconnected-(J4-Pad10)") (class "Default")
      (node (ref "J4") (pin "10") (pinfunction "10_10") (pintype "passive"))
    )
    (net (code "61") (name "unconnected-(R73-Pad1)") (class "Default")
      (node (ref "R73") (pin "1") (pinfunction "1_1") (pintype "passive"))
    )
    (net (code "62") (name "unconnected-(U1-NC-Pad20)") (class "Default")
      (node (ref "U1") (pin "20") (pinfunction "NC_20") (pintype "passive+no_connect"))
    )
    (net (code "63") (name "unconnected-(U1-NC-Pad29)") (class "Default")
      (node (ref "U1") (pin "29") (pinfunction "NC_29") (pintype "passive+no_connect"))
    )
    (net (code "64") (name "unconnected-(U1-NC-Pad33)") (class "Default")
      (node (ref "U1") (pin "33") (pinfunction "NC_33") (pintype "passive+no_connect"))
    )
    (net (code "65") (name "unconnected-(U1-NC-Pad41)") (class "Default")
      (node (ref "U1") (pin "41") (pinfunction "NC_41") (pintype "passive+no_connect"))
    )
    (net (code "66") (name "unconnected-(U1-NC-Pad45)") (class "Default")
      (node (ref "U1") (pin "45") (pinfunction "NC_45") (pintype "passive+no_connect"))
    )
    (net (code "67") (name "unconnected-(U1-RF_BG-Pad31)") (class "Default")
      (node (ref "U1") (pin "31") (pinfunction "RF_BG_31") (pintype "bidirectional+no_connect"))
    )
  )
)
